# 07_ux.net
KiCad netlist of a schematic drawn in Altium Designer
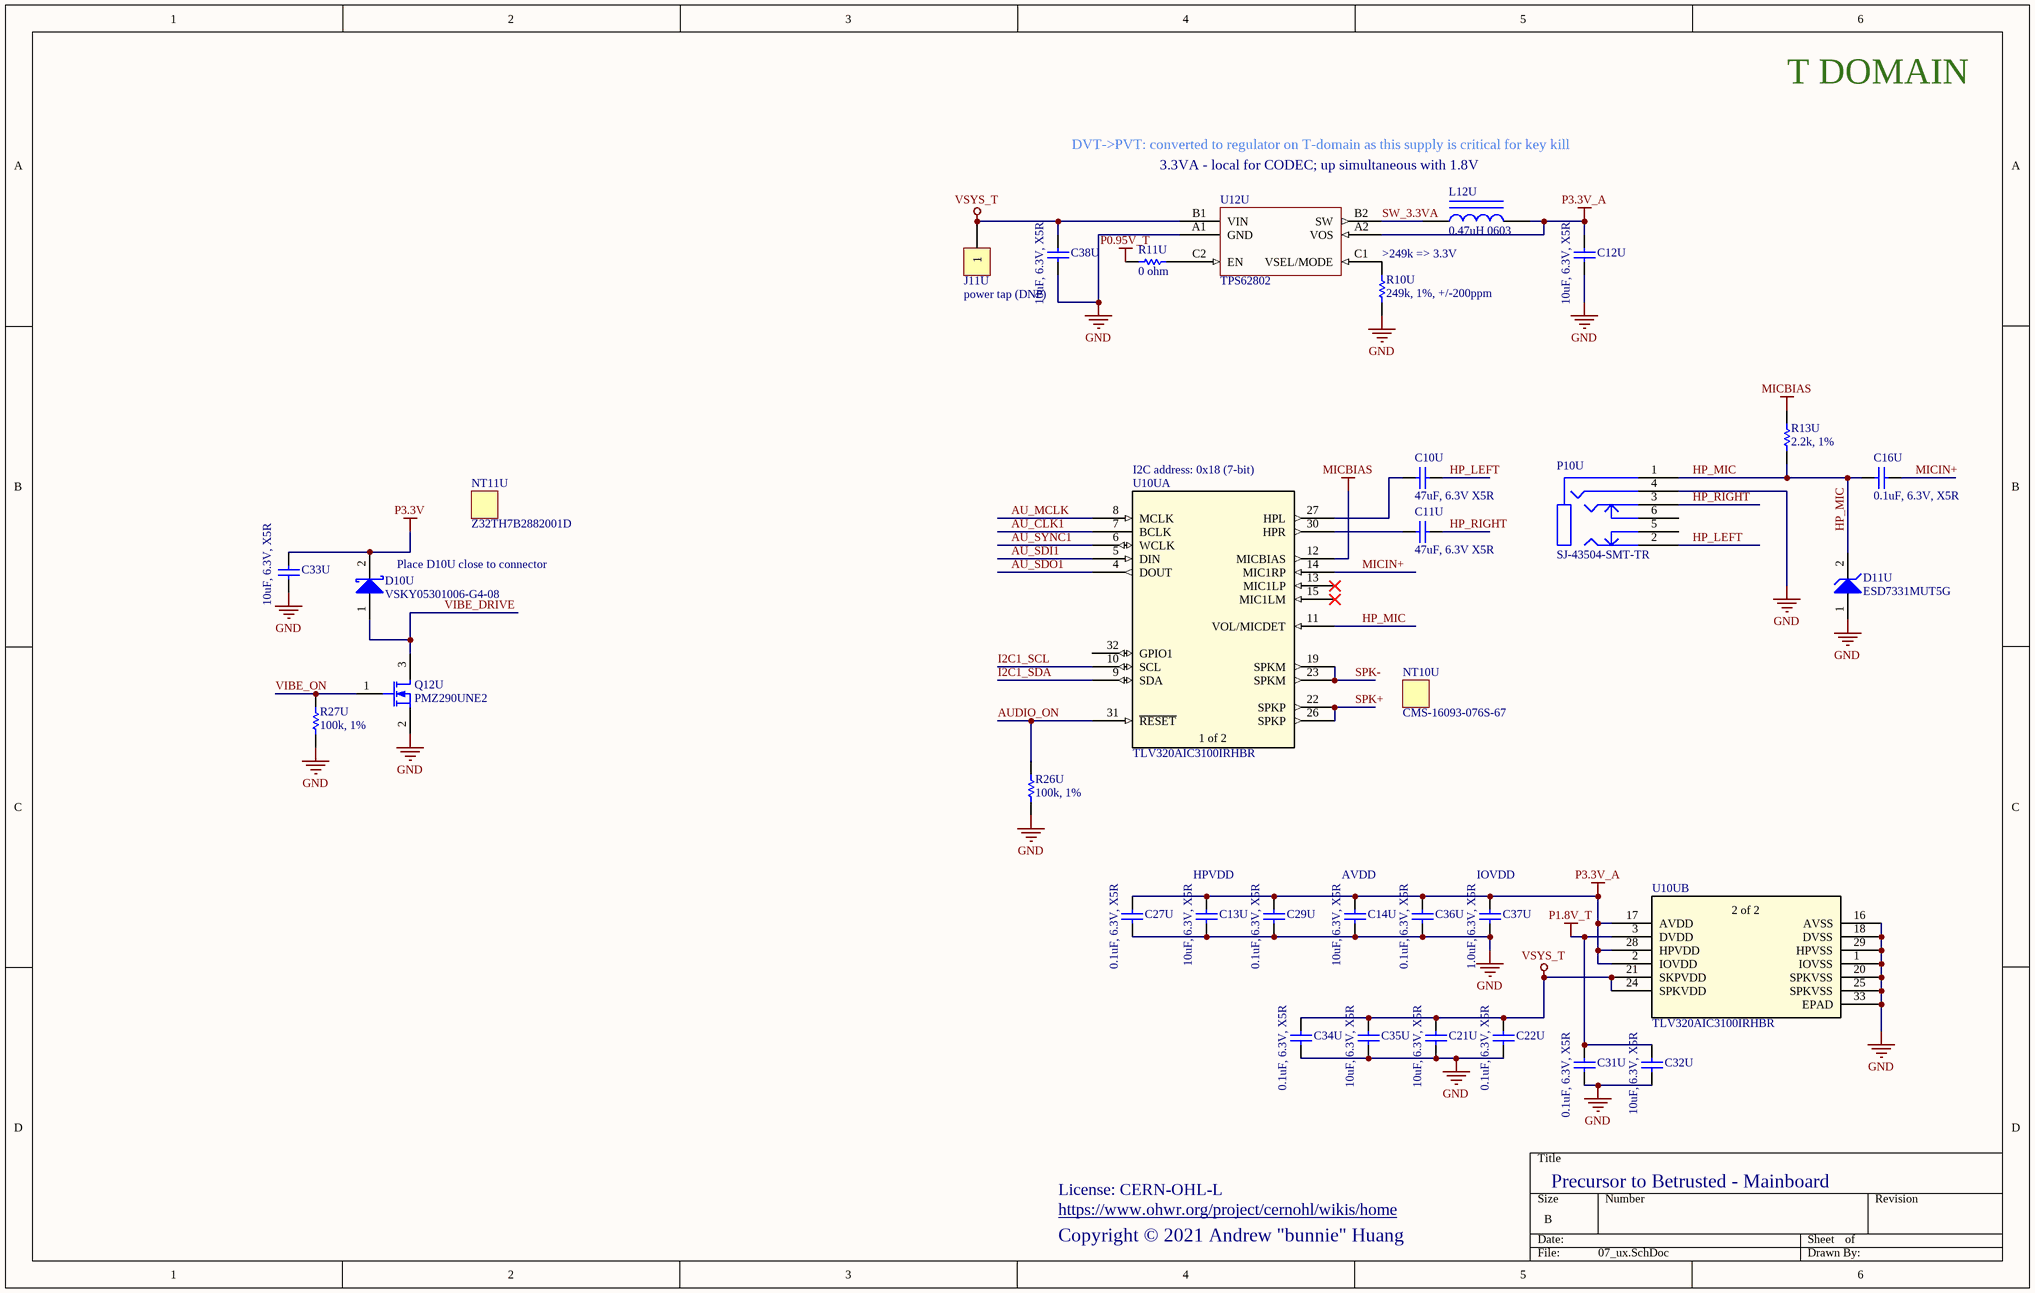
[diagram p0: 07_ux.SchDoc]

(export (version "E")
  (design (tool "Eeschema 10.0.6"))
  (components
    (comp (ref "C10U")
      (value "47uF, 6.3V X5R")
      (footprint "B_CAP0805")
      (description "Capacitor (Semiconductor SIM Model)")
      (fields (field (name "MPN") "CL21A476MQYNNNE"))
      (libsource (lib "Miscellaneous Devices") (part "Cap Semi"))
    )
    (comp (ref "C11U")
      (value "47uF, 6.3V X5R")
      (footprint "B_CAP0805")
      (description "Capacitor (Semiconductor SIM Model)")
      (fields (field (name "MPN") "CL21A476MQYNNNE"))
      (libsource (lib "Miscellaneous Devices") (part "Cap Semi"))
    )
    (comp (ref "C12U")
      (value "10uF, 6.3V, X5R")
      (footprint "B_CAP0603")
      (description "Capacitor (Semiconductor SIM Model)")
      (fields (field (name "MPN") "CL10A106MQ8NNNC"))
      (libsource (lib "Miscellaneous Devices") (part "Cap Semi"))
    )
    (comp (ref "C13U")
      (value "10uF, 6.3V, X5R")
      (footprint "B_CAP0603")
      (description "Capacitor (Semiconductor SIM Model)")
      (fields (field (name "MPN") "CL10A106MQ8NNNC"))
      (libsource (lib "Miscellaneous Devices") (part "Cap Semi"))
    )
    (comp (ref "C14U")
      (value "10uF, 6.3V, X5R")
      (footprint "B_CAP0603")
      (description "Capacitor (Semiconductor SIM Model)")
      (fields (field (name "MPN") "CL10A106MQ8NNNC"))
      (libsource (lib "Miscellaneous Devices") (part "Cap Semi"))
    )
    (comp (ref "C16U")
      (value "0.1uF, 6.3V, X5R")
      (footprint "B_CAP0201")
      (description "Capacitor (Semiconductor SIM Model)")
      (fields (field (name "MPN") "CL03A104KQ3NNNC"))
      (libsource (lib "Miscellaneous Devices") (part "Cap Semi"))
    )
    (comp (ref "C21U")
      (value "10uF, 6.3V, X5R")
      (footprint "B_CAP0603")
      (description "Capacitor (Semiconductor SIM Model)")
      (fields (field (name "MPN") "CL10A106MQ8NNNC"))
      (libsource (lib "Miscellaneous Devices") (part "Cap Semi"))
    )
    (comp (ref "C22U")
      (value "0.1uF, 6.3V, X5R")
      (footprint "B_CAP0201")
      (description "Capacitor (Semiconductor SIM Model)")
      (fields (field (name "MPN") "CL03A104KQ3NNNC"))
      (libsource (lib "Miscellaneous Devices") (part "Cap Semi"))
    )
    (comp (ref "C27U")
      (value "0.1uF, 6.3V, X5R")
      (footprint "B_CAP0201")
      (description "Capacitor (Semiconductor SIM Model)")
      (fields (field (name "MPN") "CL03A104KQ3NNNC"))
      (libsource (lib "Miscellaneous Devices") (part "Cap Semi"))
    )
    (comp (ref "C29U")
      (value "0.1uF, 6.3V, X5R")
      (footprint "B_CAP0201")
      (description "Capacitor (Semiconductor SIM Model)")
      (fields (field (name "MPN") "CL03A104KQ3NNNC"))
      (libsource (lib "Miscellaneous Devices") (part "Cap Semi"))
    )
    (comp (ref "C31U")
      (value "0.1uF, 6.3V, X5R")
      (footprint "B_CAP0201")
      (description "Capacitor (Semiconductor SIM Model)")
      (fields (field (name "MPN") "CL03A104KQ3NNNC"))
      (libsource (lib "Miscellaneous Devices") (part "Cap Semi"))
    )
    (comp (ref "C32U")
      (value "10uF, 6.3V, X5R")
      (footprint "B_CAP0603")
      (description "Capacitor (Semiconductor SIM Model)")
      (fields (field (name "MPN") "CL10A106MQ8NNNC"))
      (libsource (lib "Miscellaneous Devices") (part "Cap Semi"))
    )
    (comp (ref "C33U")
      (value "10uF, 6.3V, X5R")
      (footprint "B_CAP0603")
      (description "Capacitor (Semiconductor SIM Model)")
      (fields (field (name "MPN") "CL10A106MQ8NNNC"))
      (libsource (lib "Miscellaneous Devices") (part "Cap Semi"))
    )
    (comp (ref "C34U")
      (value "0.1uF, 6.3V, X5R")
      (footprint "B_CAP0201")
      (description "Capacitor (Semiconductor SIM Model)")
      (fields (field (name "MPN") "CL03A104KQ3NNNC"))
      (libsource (lib "Miscellaneous Devices") (part "Cap Semi"))
    )
    (comp (ref "C35U")
      (value "10uF, 6.3V, X5R")
      (footprint "B_CAP0603")
      (description "Capacitor (Semiconductor SIM Model)")
      (fields (field (name "MPN") "CL10A106MQ8NNNC"))
      (libsource (lib "Miscellaneous Devices") (part "Cap Semi"))
    )
    (comp (ref "C36U")
      (value "0.1uF, 6.3V, X5R")
      (footprint "B_CAP0201")
      (description "Capacitor (Semiconductor SIM Model)")
      (fields (field (name "MPN") "CL03A104KQ3NNNC"))
      (libsource (lib "Miscellaneous Devices") (part "Cap Semi"))
    )
    (comp (ref "C37U")
      (value "1.0uF, 6.3V, X5R")
      (footprint "B_CAP0201")
      (description "Capacitor (Semiconductor SIM Model)")
      (fields (field (name "MPN") "GRM033R60J105MEA2D"))
      (libsource (lib "Miscellaneous Devices") (part "Cap Semi"))
    )
    (comp (ref "C38U")
      (value "10uF, 6.3V, X5R")
      (footprint "B_CAP0603")
      (description "Capacitor (Semiconductor SIM Model)")
      (fields (field (name "MPN") "CL10A106MQ8NNNC"))
      (libsource (lib "Miscellaneous Devices") (part "Cap Semi"))
    )
    (comp (ref "D10U")
      (value "VSKY05301006-G4-08")
      (footprint "B_DIO0402")
      (description "Schottky Rectifier")
      (libsource (lib "Miscellaneous Devices") (part "Diode 11DQ03"))
    )
    (comp (ref "D11U")
      (value "ESD7331MUT5G")
      (footprint "D_X3DFN2_0201")
      (fields (field (name "PUBLISHER") "Altium Limited"))
      (libsource (lib "Miscellaneous Devices") (part "D Zener"))
    )
    (comp (ref "J11U")
      (value "power tap (DNP)")
      (footprint "B_PWRTAP0402")
      (description "Connector")
      (fields (field (name "MPN") "DNP"))
      (libsource (lib "*") (part "CON1"))
    )
    (comp (ref "L12U")
      (value "0.47uH 0603")
      (footprint "B_IND0603")
      (description "Magnetic-Core Inductor")
      (fields (field (name "MPN") "TFM160808ALC-R47MTAA"))
      (libsource (lib "Miscellaneous Devices") (part "Inductor Iron"))
    )
    (comp (ref "NT10U")
      (value "CMS-16093-076S-67")
      (description "Placeholder for non-board BOM items")
      (libsource (lib "commonsch") (part "NOTE"))
    )
    (comp (ref "NT11U")
      (value "Z32TH7B2882001D")
      (description "Placeholder for non-board BOM items")
      (libsource (lib "commonsch") (part "NOTE"))
    )
    (comp (ref "P10U")
      (value "SJ-43504-SMT-TR")
      (footprint "CUI_SJ_43504_SMT_TR_FLIP")
      (description "Mid mount audio jack")
      (libsource (lib "commonsch-new") (part "CUI_3.5MM_STEREO_MIC"))
    )
    (comp (ref "Q12U")
      (value "PMZ290UNE2")
      (footprint "SOT883")
      (description "N-Channel MOSFET")
      (fields (field (name "PUBLISHER") "Altium Limited"))
      (libsource (lib "Miscellaneous Devices") (part "MOSFET-N"))
    )
    (comp (ref "R10U")
      (value "249k, 1%, +/-200ppm")
      (footprint "B_RES0402")
      (description "Resistor")
      (fields (field (name "MPN") "RC0402FR-07249KL"))
      (libsource (lib "Miscellaneous Devices") (part "Res1"))
    )
    (comp (ref "R11U")
      (value "0 ohm")
      (footprint "B_RES0201")
      (description "Resistor")
      (fields (field (name "MPN") "ANY"))
      (libsource (lib "Miscellaneous Devices") (part "Res1"))
    )
    (comp (ref "R13U")
      (value "2.2k, 1%")
      (footprint "B_RES0201")
      (description "Resistor")
      (fields (field (name "MPN") "ANY"))
      (libsource (lib "Miscellaneous Devices") (part "Res1"))
    )
    (comp (ref "R26U")
      (value "100k, 1%")
      (footprint "B_RES0201")
      (description "Resistor")
      (fields (field (name "MPN") "ANY"))
      (libsource (lib "Miscellaneous Devices") (part "Res1"))
    )
    (comp (ref "R27U")
      (value "100k, 1%")
      (footprint "B_RES0201")
      (description "Resistor")
      (fields (field (name "MPN") "ANY"))
      (libsource (lib "Miscellaneous Devices") (part "Res1"))
    )
    (comp (ref "U10U")
      (value "TLV320AIC3100IRHBR")
      (footprint "TI_VQFN_RHB0032E")
      (description "Low-Power Audio Codec With Audio Processing and Mono Class-D Amplifier")
      (fields
        (field (name "MANUFACTURER") "Texas Instruments")
        (field (name "GENERIC_PART_NUMBER") "TLV320AIC3100")
        (field (name "COPYRIGHT") "Copyright (C) 2018 Accelerated Designs. All rights reserved")
      )
      (libsource (lib "commonsch-new") (part "TLV320AIC3100IRH"))
    )
    (comp (ref "U12U")
      (value "TPS62802")
      (footprint "BGA6C35P2X3_70X105X40_NSMD")
      (description "Buck regulator, 4MHz, 0.6A, 1.8V-3.3V, low Iq")
      (fields (field (name "MPN") "TPS62802YKAR"))
      (libsource (lib "altium-import") (part "root_0_TPS62802_"))
    )
  )
  (nets
    (net (code "1") (name "/AUDIO_ON") (class "Default")
      (node (ref "R26U") (pin "2") (pinfunction "2_2") (pintype "passive"))
      (node (ref "U10U") (pin "31") (pinfunction "~{RESET}_31") (pintype "input"))
    )
    (net (code "2") (name "/AU_CLK1") (class "Default")
      (node (ref "U10U") (pin "7") (pinfunction "BCLK_7") (pintype "passive"))
    )
    (net (code "3") (name "/AU_MCLK") (class "Default")
      (node (ref "U10U") (pin "8") (pinfunction "MCLK_8") (pintype "input"))
    )
    (net (code "4") (name "/AU_SDI1") (class "Default")
      (node (ref "U10U") (pin "5") (pinfunction "DIN_5") (pintype "input"))
    )
    (net (code "5") (name "/AU_SDO1") (class "Default")
      (node (ref "U10U") (pin "4") (pinfunction "DOUT_4") (pintype "output"))
    )
    (net (code "6") (name "/AU_SYNC1") (class "Default")
      (node (ref "U10U") (pin "6") (pinfunction "WCLK_6") (pintype "bidirectional"))
    )
    (net (code "7") (name "/HP_LEFT") (class "Default")
      (node (ref "C10U") (pin "2") (pinfunction "2_2") (pintype "passive"))
      (node (ref "P10U") (pin "2") (pinfunction "TIP_2") (pintype "passive"))
    )
    (net (code "8") (name "/HP_MIC") (class "Default")
      (node (ref "C16U") (pin "1") (pinfunction "1_1") (pintype "passive"))
      (node (ref "D11U") (pin "2") (pinfunction "K_2") (pintype "passive"))
      (node (ref "P10U") (pin "1") (pinfunction "SLEEVE_1") (pintype "passive"))
      (node (ref "R13U") (pin "1") (pinfunction "1_1") (pintype "passive"))
      (node (ref "U10U") (pin "11") (pinfunction "VOL/MICDET_11") (pintype "input"))
    )
    (net (code "9") (name "/HP_RIGHT") (class "Default")
      (node (ref "C11U") (pin "2") (pinfunction "2_2") (pintype "passive"))
      (node (ref "P10U") (pin "3") (pinfunction "RING1_3") (pintype "passive"))
    )
    (net (code "10") (name "/I2C1_SCL") (class "Default")
      (node (ref "U10U") (pin "10") (pinfunction "SCL_10") (pintype "bidirectional"))
    )
    (net (code "11") (name "/I2C1_SDA") (class "Default")
      (node (ref "U10U") (pin "9") (pinfunction "SDA_9") (pintype "bidirectional"))
    )
    (net (code "12") (name "/MICIN+") (class "Default")
      (node (ref "C16U") (pin "2") (pinfunction "2_2") (pintype "passive"))
      (node (ref "U10U") (pin "14") (pinfunction "MIC1RP_14") (pintype "input"))
    )
    (net (code "13") (name "/SPK+") (class "Default")
      (node (ref "U10U") (pin "22") (pinfunction "SPKP_22") (pintype "output"))
      (node (ref "U10U") (pin "26") (pinfunction "SPKP_26") (pintype "output"))
    )
    (net (code "14") (name "/SPK-") (class "Default")
      (node (ref "U10U") (pin "19") (pinfunction "SPKM_19") (pintype "output"))
      (node (ref "U10U") (pin "23") (pinfunction "SPKM_23") (pintype "output"))
    )
    (net (code "15") (name "/SW_3.3VA") (class "Default")
      (node (ref "L12U") (pin "1") (pinfunction "1_1") (pintype "passive"))
      (node (ref "U12U") (pin "B2") (pinfunction "SW_B2") (pintype "output"))
    )
    (net (code "16") (name "/VIBE_DRIVE") (class "Default")
      (node (ref "D10U") (pin "1") (pinfunction "A_1") (pintype "passive"))
      (node (ref "Q12U") (pin "3") (pinfunction "D_3") (pintype "passive"))
    )
    (net (code "17") (name "/VIBE_ON") (class "Default")
      (node (ref "Q12U") (pin "1") (pinfunction "G_1") (pintype "passive"))
      (node (ref "R27U") (pin "2") (pinfunction "2_2") (pintype "passive"))
    )
    (net (code "18") (name "GND") (class "Default")
      (node (ref "C12U") (pin "2") (pinfunction "2_2") (pintype "passive"))
      (node (ref "C13U") (pin "2") (pinfunction "2_2") (pintype "passive"))
      (node (ref "C14U") (pin "2") (pinfunction "2_2") (pintype "passive"))
      (node (ref "C21U") (pin "2") (pinfunction "2_2") (pintype "passive"))
      (node (ref "C22U") (pin "2") (pinfunction "2_2") (pintype "passive"))
      (node (ref "C27U") (pin "2") (pinfunction "2_2") (pintype "passive"))
      (node (ref "C29U") (pin "2") (pinfunction "2_2") (pintype "passive"))
      (node (ref "C31U") (pin "2") (pinfunction "2_2") (pintype "passive"))
      (node (ref "C32U") (pin "2") (pinfunction "2_2") (pintype "passive"))
      (node (ref "C33U") (pin "1") (pinfunction "1_1") (pintype "passive"))
      (node (ref "C34U") (pin "2") (pinfunction "2_2") (pintype "passive"))
      (node (ref "C35U") (pin "2") (pinfunction "2_2") (pintype "passive"))
      (node (ref "C36U") (pin "2") (pinfunction "2_2") (pintype "passive"))
      (node (ref "C37U") (pin "1") (pinfunction "1_1") (pintype "passive"))
      (node (ref "C38U") (pin "2") (pinfunction "2_2") (pintype "passive"))
      (node (ref "D11U") (pin "1") (pinfunction "A_1") (pintype "passive"))
      (node (ref "P10U") (pin "4") (pinfunction "RING2_4") (pintype "passive"))
      (node (ref "Q12U") (pin "2") (pinfunction "S_2") (pintype "passive"))
      (node (ref "R10U") (pin "2") (pinfunction "2_2") (pintype "passive"))
      (node (ref "R26U") (pin "1") (pinfunction "1_1") (pintype "passive"))
      (node (ref "R27U") (pin "1") (pinfunction "1_1") (pintype "passive"))
      (node (ref "U10U") (pin "1") (pinfunction "IOVSS_1") (pintype "power_in"))
      (node (ref "U10U") (pin "16") (pinfunction "AVSS_16") (pintype "power_in"))
      (node (ref "U10U") (pin "18") (pinfunction "DVSS_18") (pintype "power_in"))
      (node (ref "U10U") (pin "20") (pinfunction "SPKVSS_20") (pintype "power_in"))
      (node (ref "U10U") (pin "25") (pinfunction "SPKVSS_25") (pintype "power_in"))
      (node (ref "U10U") (pin "29") (pinfunction "HPVSS_29") (pintype "power_in"))
      (node (ref "U10U") (pin "33") (pinfunction "EPAD_33") (pintype "power_in"))
      (node (ref "U12U") (pin "A1") (pinfunction "GND_A1") (pintype "power_in"))
    )
    (net (code "19") (name "MICBIAS") (class "Default")
      (node (ref "R13U") (pin "2") (pinfunction "2_2") (pintype "passive"))
      (node (ref "U10U") (pin "12") (pinfunction "MICBIAS_12") (pintype "output"))
    )
    (net (code "20") (name "Net-(U10UA-HPL)") (class "Default")
      (node (ref "C10U") (pin "1") (pinfunction "1_1") (pintype "passive"))
      (node (ref "U10U") (pin "27") (pinfunction "HPL_27") (pintype "output"))
    )
    (net (code "21") (name "Net-(U10UA-HPR)") (class "Default")
      (node (ref "C11U") (pin "1") (pinfunction "1_1") (pintype "passive"))
      (node (ref "U10U") (pin "30") (pinfunction "HPR_30") (pintype "output"))
    )
    (net (code "22") (name "Net-(U12U-EN)") (class "Default")
      (node (ref "R11U") (pin "2") (pinfunction "2_2") (pintype "passive"))
      (node (ref "U12U") (pin "C2") (pinfunction "EN_C2") (pintype "input"))
    )
    (net (code "23") (name "Net-(U12U-VSEL{slash}MODE)") (class "Default")
      (node (ref "R10U") (pin "1") (pinfunction "1_1") (pintype "passive"))
      (node (ref "U12U") (pin "C1") (pinfunction "VSEL/MODE_C1") (pintype "input"))
    )
    (net (code "24") (name "P0.95V_T") (class "Default")
      (node (ref "R11U") (pin "1") (pinfunction "1_1") (pintype "passive"))
    )
    (net (code "25") (name "P1.8V_T") (class "Default")
      (node (ref "C31U") (pin "1") (pinfunction "1_1") (pintype "passive"))
      (node (ref "C32U") (pin "1") (pinfunction "1_1") (pintype "passive"))
      (node (ref "U10U") (pin "3") (pinfunction "DVDD_3") (pintype "power_in"))
    )
    (net (code "26") (name "P3.3V") (class "Default")
      (node (ref "C33U") (pin "2") (pinfunction "2_2") (pintype "passive"))
      (node (ref "D10U") (pin "2") (pinfunction "K_2") (pintype "passive"))
    )
    (net (code "27") (name "P3.3V_A") (class "Default")
      (node (ref "C12U") (pin "1") (pinfunction "1_1") (pintype "passive"))
      (node (ref "C13U") (pin "1") (pinfunction "1_1") (pintype "passive"))
      (node (ref "C14U") (pin "1") (pinfunction "1_1") (pintype "passive"))
      (node (ref "C27U") (pin "1") (pinfunction "1_1") (pintype "passive"))
      (node (ref "C29U") (pin "1") (pinfunction "1_1") (pintype "passive"))
      (node (ref "C36U") (pin "1") (pinfunction "1_1") (pintype "passive"))
      (node (ref "C37U") (pin "2") (pinfunction "2_2") (pintype "passive"))
      (node (ref "L12U") (pin "2") (pinfunction "2_2") (pintype "passive"))
      (node (ref "U10U") (pin "17") (pinfunction "AVDD_17") (pintype "power_in"))
      (node (ref "U10U") (pin "2") (pinfunction "IOVDD_2") (pintype "power_in"))
      (node (ref "U10U") (pin "28") (pinfunction "HPVDD_28") (pintype "power_in"))
      (node (ref "U12U") (pin "A2") (pinfunction "VOS_A2") (pintype "input"))
    )
    (net (code "28") (name "VSYS_T") (class "Default")
      (node (ref "C21U") (pin "1") (pinfunction "1_1") (pintype "passive"))
      (node (ref "C22U") (pin "1") (pinfunction "1_1") (pintype "passive"))
      (node (ref "C34U") (pin "1") (pinfunction "1_1") (pintype "passive"))
      (node (ref "C35U") (pin "1") (pinfunction "1_1") (pintype "passive"))
      (node (ref "C38U") (pin "1") (pinfunction "1_1") (pintype "passive"))
      (node (ref "J11U") (pin "1") (pinfunction "1_1") (pintype "passive"))
      (node (ref "U10U") (pin "21") (pinfunction "SKPVDD_21") (pintype "power_in"))
      (node (ref "U10U") (pin "24") (pinfunction "SPKVDD_24") (pintype "power_in"))
      (node (ref "U12U") (pin "B1") (pinfunction "VIN_B1") (pintype "power_in"))
    )
    (net (code "29") (name "unconnected-(P10U-RING1_SW-Pad6)") (class "Default")
      (node (ref "P10U") (pin "6") (pinfunction "RING1_SW_6") (pintype "passive"))
    )
    (net (code "30") (name "unconnected-(P10U-TIP_SW-Pad5)") (class "Default")
      (node (ref "P10U") (pin "5") (pinfunction "TIP_SW_5") (pintype "passive"))
    )
    (net (code "31") (name "unconnected-(U10UA-GPIO1-Pad32)") (class "Default")
      (node (ref "U10U") (pin "32") (pinfunction "GPIO1_32") (pintype "bidirectional"))
    )
    (net (code "32") (name "unconnected-(U10UA-MIC1LM-Pad15)") (class "Default")
      (node (ref "U10U") (pin "15") (pinfunction "MIC1LM_15") (pintype "input+no_connect"))
    )
    (net (code "33") (name "unconnected-(U10UA-MIC1LP-Pad13)") (class "Default")
      (node (ref "U10U") (pin "13") (pinfunction "MIC1LP_13") (pintype "input+no_connect"))
    )
  )
)
